# RPi-HAT_BUS-Controller_V0_7.net
KiCad netlist of a schematic drawn in EAGLE
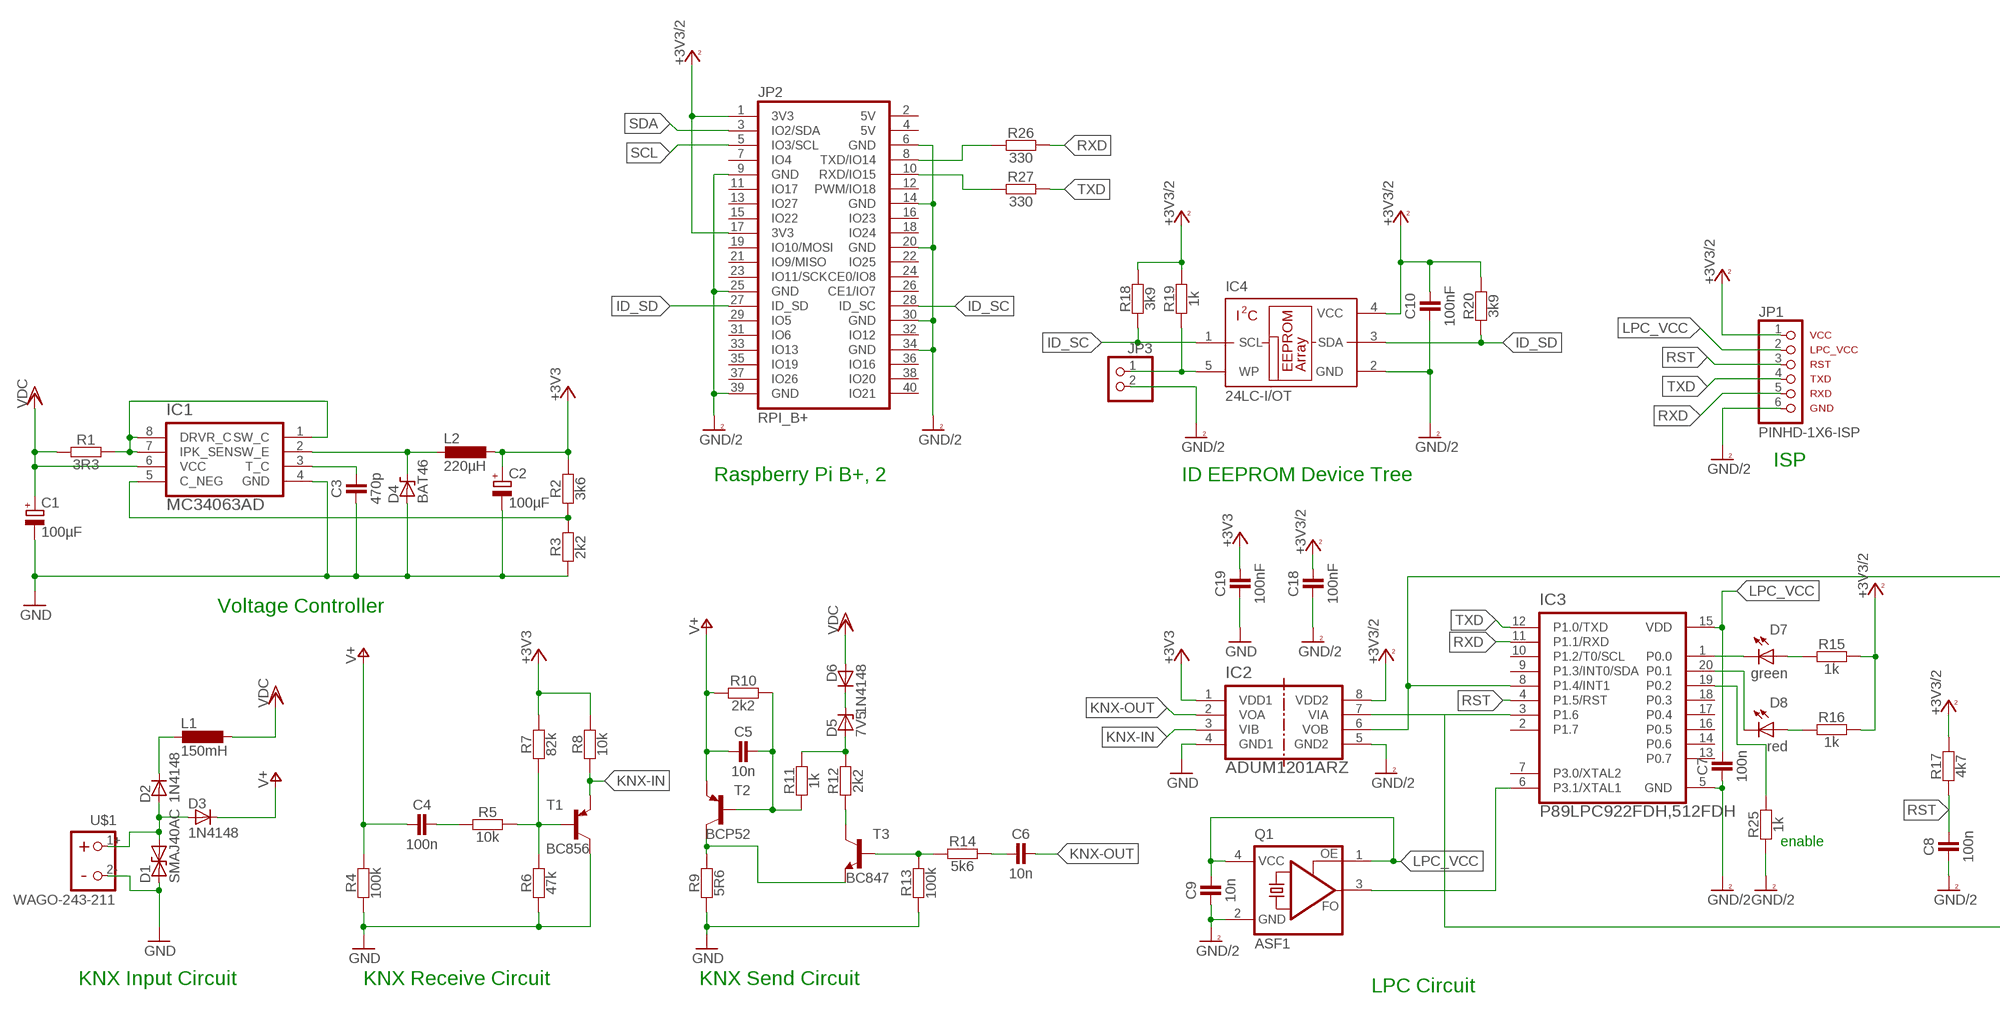
[diagram p0: schematic, sheet 1, part 1 of 2]
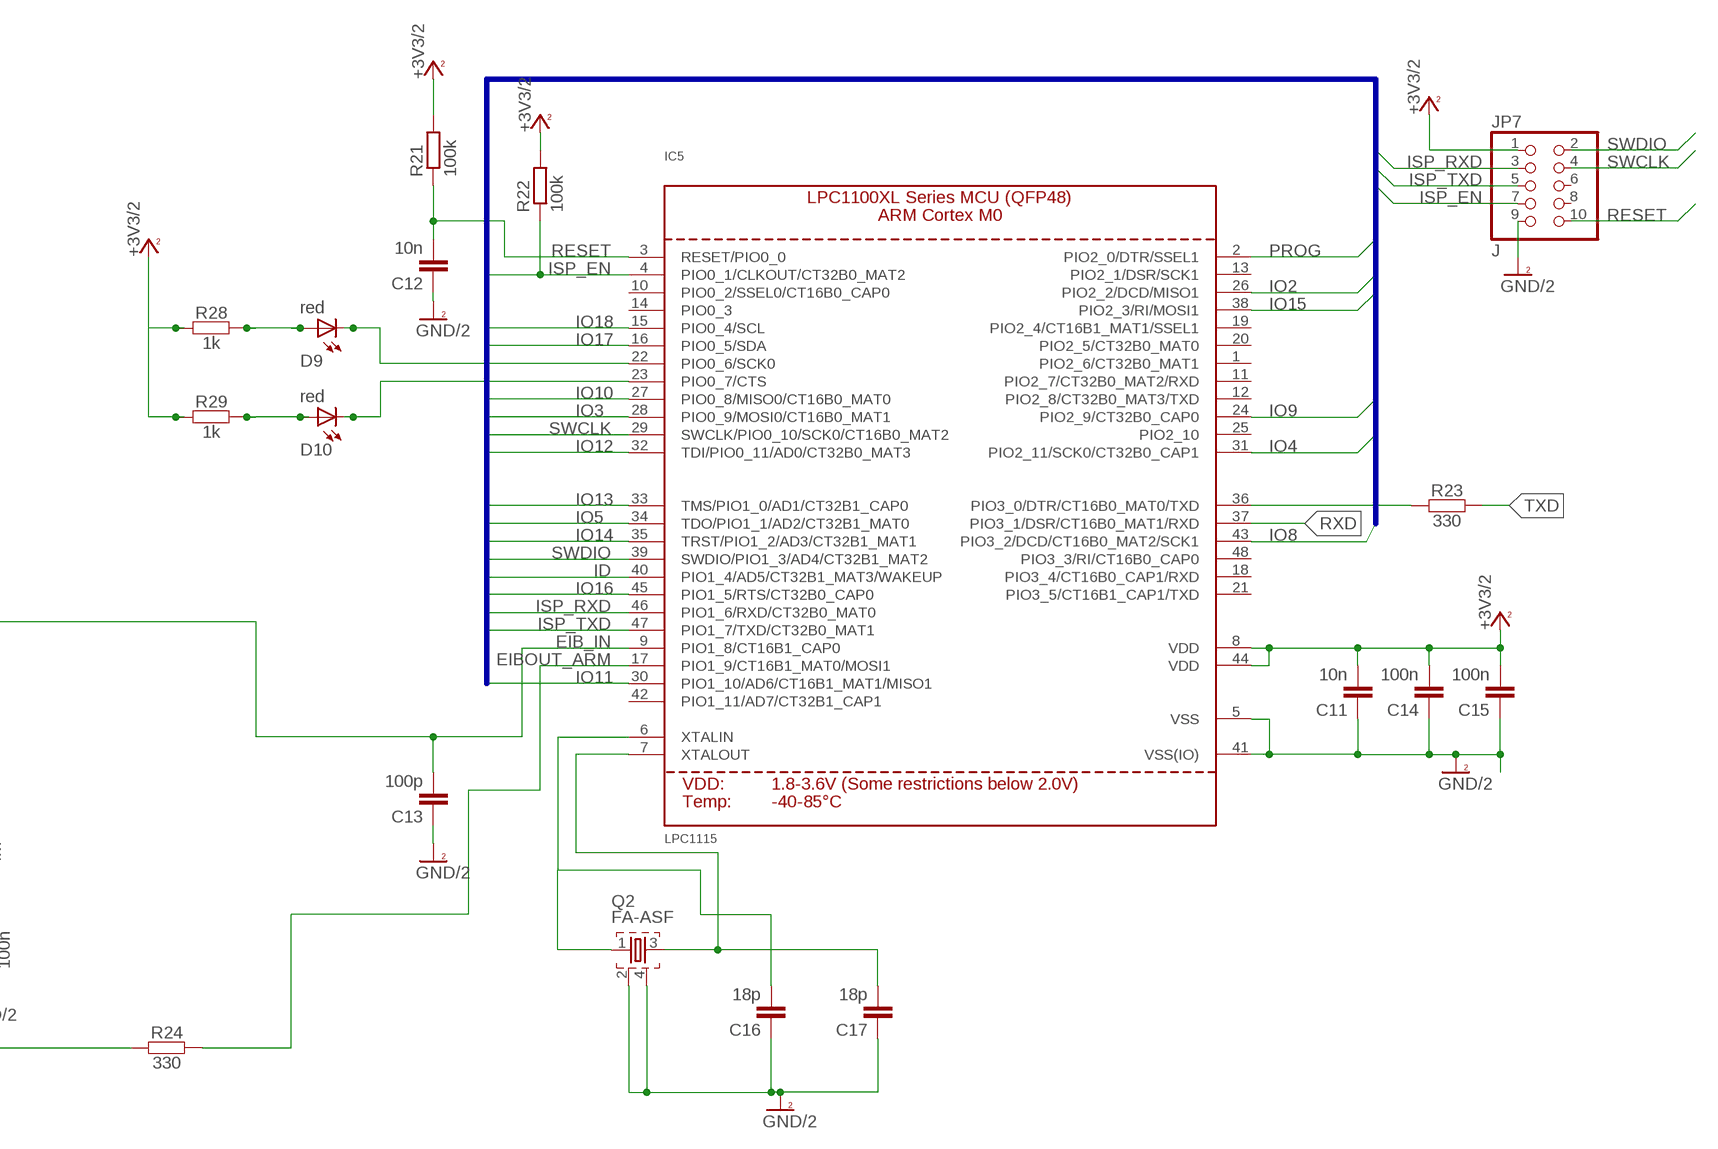
[diagram p1: schematic, sheet 1, part 2 of 2]

(export (version "E")
  (design (tool "Eeschema 10.0.6"))
  (components
    (comp (ref "C1")
      (value "100µF")
      (footprint "eagle-import:PANASONIC_D")
      (libsource (lib "eagle-import") (part "100µF,35V"))
    )
    (comp (ref "C2")
      (value "100µF")
      (footprint "eagle-import:PANASONIC_C")
      (libsource (lib "eagle-import") (part "100µF,6.3V"))
    )
    (comp (ref "C3")
      (value "470p")
      (footprint "eagle-import:R1206")
      (libsource (lib "eagle-import") (part "CAPACITORC1206"))
    )
    (comp (ref "C4")
      (value "100n")
      (footprint "eagle-import:R1206")
      (libsource (lib "eagle-import") (part "CAPACITORC1206"))
    )
    (comp (ref "C5")
      (value "10n")
      (footprint "eagle-import:R1206")
      (libsource (lib "eagle-import") (part "CAPACITORC1206"))
    )
    (comp (ref "C6")
      (value "10n")
      (footprint "eagle-import:R1206")
      (libsource (lib "eagle-import") (part "CAPACITORC1206"))
    )
    (comp (ref "C7")
      (value "100n")
      (footprint "eagle-import:R1206")
      (libsource (lib "eagle-import") (part "CAPACITORC1206"))
    )
    (comp (ref "C8")
      (value "100n")
      (footprint "eagle-import:R1206")
      (libsource (lib "eagle-import") (part "CAPACITORC1206"))
    )
    (comp (ref "C9")
      (value "10n")
      (footprint "eagle-import:R1206")
      (libsource (lib "eagle-import") (part "CAPACITORC1206"))
    )
    (comp (ref "C10")
      (value "100nF")
      (footprint "eagle-import:R1206")
      (libsource (lib "eagle-import") (part "CAPACITORC1206"))
    )
    (comp (ref "C11")
      (value "10n")
      (footprint "eagle-import:C1206")
      (libsource (lib "eagle-import") (part "C-EUC1206"))
    )
    (comp (ref "C12")
      (value "10n")
      (footprint "eagle-import:C1206")
      (libsource (lib "eagle-import") (part "C-EUC1206"))
    )
    (comp (ref "C13")
      (value "100p")
      (footprint "eagle-import:C1206")
      (libsource (lib "eagle-import") (part "C-EUC1206"))
    )
    (comp (ref "C14")
      (value "100n")
      (footprint "eagle-import:C1206")
      (libsource (lib "eagle-import") (part "C-EUC1206"))
    )
    (comp (ref "C15")
      (value "100n")
      (footprint "eagle-import:C1206")
      (libsource (lib "eagle-import") (part "C-EUC1206"))
    )
    (comp (ref "C16")
      (value "18p")
      (footprint "eagle-import:C1206")
      (libsource (lib "eagle-import") (part "C-EUC1206"))
    )
    (comp (ref "C17")
      (value "18p")
      (footprint "eagle-import:C1206")
      (libsource (lib "eagle-import") (part "C-EUC1206"))
    )
    (comp (ref "C18")
      (value "100nF")
      (footprint "eagle-import:R1206")
      (libsource (lib "eagle-import") (part "CAPACITORC1206"))
    )
    (comp (ref "C19")
      (value "100nF")
      (footprint "eagle-import:R1206")
      (libsource (lib "eagle-import") (part "CAPACITORC1206"))
    )
    (comp (ref "D1")
      (value "SMAJ40AC")
      (footprint "eagle-import:DO-214AC")
      (libsource (lib "eagle-import") (part "SMAJ40AC"))
    )
    (comp (ref "D2")
      (value "1N4148")
      (footprint "eagle-import:MINIMELF")
      (libsource (lib "eagle-import") (part "1N4148MINIMELF"))
    )
    (comp (ref "D3")
      (value "1N4148")
      (footprint "eagle-import:MINIMELF")
      (libsource (lib "eagle-import") (part "1N4148MINIMELF"))
    )
    (comp (ref "D4")
      (value "BAT46")
      (footprint "eagle-import:MINIMELF")
      (libsource (lib "eagle-import") (part "BAT46"))
    )
    (comp (ref "D5")
      (value "7V5")
      (footprint "eagle-import:MINIMELF")
      (libsource (lib "eagle-import") (part "Z-DIODE"))
    )
    (comp (ref "D6")
      (value "1N4148")
      (footprint "eagle-import:MINIMELF")
      (libsource (lib "eagle-import") (part "Diode_for_Selfbus-Projects_1N4148MINIMELF"))
    )
    (comp (ref "D7")
      (value "green")
      (footprint "eagle-import:CHIPLED_1206")
      (libsource (lib "eagle-import") (part "LED1206"))
    )
    (comp (ref "D8")
      (value "red")
      (footprint "eagle-import:CHIPLED_1206")
      (libsource (lib "eagle-import") (part "LED1206"))
    )
    (comp (ref "D9")
      (value "red")
      (footprint "eagle-import:CHIPLED_1206")
      (libsource (lib "eagle-import") (part "LED1206"))
    )
    (comp (ref "D10")
      (value "red")
      (footprint "eagle-import:CHIPLED_1206")
      (libsource (lib "eagle-import") (part "LED1206"))
    )
    (comp (ref "IC1")
      (value "MC34063AD")
      (footprint "eagle-import:SOIC127P600X175-8N")
      (libsource (lib "eagle-import") (part "MC34063AD"))
    )
    (comp (ref "IC2")
      (value "ADUM1201ARZ")
      (footprint "eagle-import:SOIC127P600X175-8N")
      (libsource (lib "eagle-import") (part "ADUM1201ARZ"))
    )
    (comp (ref "IC3")
      (value "P89LPC922FDH,512FDH")
      (footprint "eagle-import:SOP65P640X110-20N")
      (fields (field (name "MPN") "P89LPC922FDH,512"))
      (libsource (lib "eagle-import") (part "P89LPC922FDH,512FDH"))
    )
    (comp (ref "IC4")
      (value "24LC-I/OT")
      (footprint "eagle-import:SOT23-5")
      (libsource (lib "eagle-import") (part "24LC-I/OT"))
    )
    (comp (ref "IC5")
      (value "LPC1115")
      (footprint "eagle-import:LQFP48")
      (libsource (lib "eagle-import") (part "LPC1113/4/5_QFP48_XLSERIES"))
    )
    (comp (ref "JP1")
      (value "PINHD-1X6-ISP")
      (footprint "eagle-import:1X06")
      (libsource (lib "eagle-import") (part "PINHD-1X6-ISP"))
    )
    (comp (ref "JP2")
      (value "RPI_B+")
      (footprint "eagle-import:RPI-B+HAT")
      (libsource (lib "eagle-import") (part "RPI_B+"))
    )
    (comp (ref "JP3")
      (value "PINHD-1X2")
      (footprint "eagle-import:1X02")
      (libsource (lib "eagle-import") (part "PINHD-1X2"))
    )
    (comp (ref "JP7")
      (value "J")
      (footprint "eagle-import:2X05M")
      (libsource (lib "eagle-import") (part "PINHD-2X05_2.00"))
    )
    (comp (ref "L1")
      (value "150mH")
      (footprint "eagle-import:11P-L1")
      (libsource (lib "eagle-import") (part "150MH-L11PL1"))
    )
    (comp (ref "L2")
      (value "220µH")
      (footprint "eagle-import:2200-11.43")
      (libsource (lib "eagle-import") (part "220µH-SMCC11.43"))
    )
    (comp (ref "Q1")
      (value "ASF1")
      (footprint "eagle-import:ASF")
      (libsource (lib "eagle-import") (part "ASF1"))
    )
    (comp (ref "Q2")
      (value "FA-ASF")
      (footprint "eagle-import:ASF")
      (libsource (lib "eagle-import") (part "FA-ASF"))
    )
    (comp (ref "R1")
      (value "3R3")
      (footprint "eagle-import:R1206")
      (libsource (lib "eagle-import") (part "RESISTORR1206"))
    )
    (comp (ref "R2")
      (value "3k6")
      (footprint "eagle-import:R1206")
      (libsource (lib "eagle-import") (part "RESISTORR1206"))
    )
    (comp (ref "R3")
      (value "2k2")
      (footprint "eagle-import:R1206")
      (libsource (lib "eagle-import") (part "RESISTORR1206"))
    )
    (comp (ref "R4")
      (value "100k")
      (footprint "eagle-import:R1206")
      (libsource (lib "eagle-import") (part "RESISTORR1206"))
    )
    (comp (ref "R5")
      (value "10k")
      (footprint "eagle-import:R1206")
      (libsource (lib "eagle-import") (part "RESISTORR1206"))
    )
    (comp (ref "R6")
      (value "47k")
      (footprint "eagle-import:R1206")
      (libsource (lib "eagle-import") (part "RESISTORR1206"))
    )
    (comp (ref "R7")
      (value "82k")
      (footprint "eagle-import:R1206")
      (libsource (lib "eagle-import") (part "RESISTORR1206"))
    )
    (comp (ref "R8")
      (value "10k")
      (footprint "eagle-import:R1206")
      (libsource (lib "eagle-import") (part "RESISTORR1206"))
    )
    (comp (ref "R9")
      (value "5R6")
      (footprint "eagle-import:R1206")
      (libsource (lib "eagle-import") (part "RESISTORR1206"))
    )
    (comp (ref "R10")
      (value "2k2")
      (footprint "eagle-import:R1206")
      (libsource (lib "eagle-import") (part "RESISTORR1206"))
    )
    (comp (ref "R11")
      (value "1k")
      (footprint "eagle-import:R1206")
      (libsource (lib "eagle-import") (part "RESISTORR1206"))
    )
    (comp (ref "R12")
      (value "2k2")
      (footprint "eagle-import:R1206")
      (libsource (lib "eagle-import") (part "RESISTORR1206"))
    )
    (comp (ref "R13")
      (value "100k")
      (footprint "eagle-import:R1206")
      (libsource (lib "eagle-import") (part "RESISTORR1206"))
    )
    (comp (ref "R14")
      (value "5k6")
      (footprint "eagle-import:R1206")
      (libsource (lib "eagle-import") (part "RESISTORR1206"))
    )
    (comp (ref "R15")
      (value "1k")
      (footprint "eagle-import:R1206")
      (libsource (lib "eagle-import") (part "RESISTORR1206"))
    )
    (comp (ref "R16")
      (value "1k")
      (footprint "eagle-import:R1206")
      (libsource (lib "eagle-import") (part "RESISTORR1206"))
    )
    (comp (ref "R17")
      (value "4k7")
      (footprint "eagle-import:R1206")
      (libsource (lib "eagle-import") (part "RESISTORR1206"))
    )
    (comp (ref "R18")
      (value "3k9")
      (footprint "eagle-import:R1206")
      (libsource (lib "eagle-import") (part "RESISTORR1206"))
    )
    (comp (ref "R19")
      (value "1k")
      (footprint "eagle-import:R1206")
      (libsource (lib "eagle-import") (part "RESISTORR1206"))
    )
    (comp (ref "R20")
      (value "3k9")
      (footprint "eagle-import:R1206")
      (libsource (lib "eagle-import") (part "RESISTORR1206"))
    )
    (comp (ref "R21")
      (value "100k")
      (footprint "eagle-import:R1206")
      (libsource (lib "eagle-import") (part "R-EU_R1206"))
    )
    (comp (ref "R22")
      (value "100k")
      (footprint "eagle-import:R1206")
      (libsource (lib "eagle-import") (part "R-EU_R1206"))
    )
    (comp (ref "R23")
      (value "330")
      (footprint "eagle-import:R1206")
      (libsource (lib "eagle-import") (part "RESISTORR1206"))
    )
    (comp (ref "R24")
      (value "330")
      (footprint "eagle-import:R1206")
      (libsource (lib "eagle-import") (part "RESISTORR1206"))
    )
    (comp (ref "R25")
      (value "1k")
      (footprint "eagle-import:R1206")
      (libsource (lib "eagle-import") (part "RESISTORR1206"))
    )
    (comp (ref "R26")
      (value "330")
      (footprint "eagle-import:R1206")
      (libsource (lib "eagle-import") (part "RESISTORR1206"))
    )
    (comp (ref "R27")
      (value "330")
      (footprint "eagle-import:R1206")
      (libsource (lib "eagle-import") (part "RESISTORR1206"))
    )
    (comp (ref "R28")
      (value "1k")
      (footprint "eagle-import:R1206")
      (libsource (lib "eagle-import") (part "RESISTORR1206"))
    )
    (comp (ref "R29")
      (value "1k")
      (footprint "eagle-import:R1206")
      (libsource (lib "eagle-import") (part "RESISTORR1206"))
    )
    (comp (ref "T1")
      (value "BC856")
      (footprint "eagle-import:SOT23")
      (libsource (lib "eagle-import") (part "PNPBC856"))
    )
    (comp (ref "T2")
      (value "BCP52")
      (footprint "eagle-import:SOT223")
      (libsource (lib "eagle-import") (part "PNPBCP52"))
    )
    (comp (ref "T3")
      (value "BC847")
      (footprint "eagle-import:SOT23")
      (libsource (lib "eagle-import") (part "NPN-BC847"))
    )
    (comp (ref "U$1")
      (value "WAGO-243-211")
      (footprint "eagle-import:WAGO-243-211")
      (libsource (lib "eagle-import") (part "WAGO-243-211"))
    )
  )
  (nets
    (net (code "1") (name "+3V3") (class "Default")
      (node (ref "C19") (pin "2") (pinfunction "2_2") (pintype "passive"))
      (node (ref "C2") (pin "+") (pinfunction "+_+") (pintype "passive"))
      (node (ref "IC2") (pin "1") (pinfunction "VDD1_1") (pintype "power_in"))
      (node (ref "L2") (pin "1") (pinfunction "1_1") (pintype "passive"))
      (node (ref "R2") (pin "2") (pinfunction "2_2") (pintype "passive"))
      (node (ref "R7") (pin "2") (pinfunction "2_2") (pintype "passive"))
      (node (ref "R8") (pin "2") (pinfunction "2_2") (pintype "passive"))
    )
    (net (code "2") (name "+3V3{slash}2") (class "Default")
      (node (ref "C10") (pin "2") (pinfunction "2_2") (pintype "passive"))
      (node (ref "C11") (pin "2") (pinfunction "2_2") (pintype "passive"))
      (node (ref "C14") (pin "2") (pinfunction "2_2") (pintype "passive"))
      (node (ref "C15") (pin "2") (pinfunction "2_2") (pintype "passive"))
      (node (ref "C18") (pin "2") (pinfunction "2_2") (pintype "passive"))
      (node (ref "IC2") (pin "8") (pinfunction "VDD2_8") (pintype "power_in"))
      (node (ref "IC4") (pin "4") (pinfunction "VCC_4") (pintype "power_in"))
      (node (ref "IC5") (pin "44") (pinfunction "VDD_44") (pintype "power_in"))
      (node (ref "IC5") (pin "8") (pinfunction "VDD_8") (pintype "power_in"))
      (node (ref "JP1") (pin "1") (pinfunction "1_1") (pintype "passive"))
      (node (ref "JP2") (pin "1") (pinfunction "3V3_1") (pintype "passive"))
      (node (ref "JP2") (pin "17") (pinfunction "3V3_17") (pintype "passive"))
      (node (ref "JP7") (pin "1") (pinfunction "1_1") (pintype "passive"))
      (node (ref "R15") (pin "2") (pinfunction "2_2") (pintype "passive"))
      (node (ref "R16") (pin "2") (pinfunction "2_2") (pintype "passive"))
      (node (ref "R17") (pin "2") (pinfunction "2_2") (pintype "passive"))
      (node (ref "R18") (pin "2") (pinfunction "2_2") (pintype "passive"))
      (node (ref "R19") (pin "2") (pinfunction "2_2") (pintype "passive"))
      (node (ref "R20") (pin "2") (pinfunction "2_2") (pintype "passive"))
      (node (ref "R21") (pin "2") (pinfunction "2_2") (pintype "passive"))
      (node (ref "R22") (pin "2") (pinfunction "2_2") (pintype "passive"))
      (node (ref "R28") (pin "1") (pinfunction "1_1") (pintype "passive"))
      (node (ref "R29") (pin "1") (pinfunction "1_1") (pintype "passive"))
    )
    (net (code "3") (name "/EIBOUT_ARM") (class "Default")
      (node (ref "IC5") (pin "17") (pinfunction "PIO1_9/CT16B1_MAT0/MOSI1_17") (pintype "bidirectional"))
      (node (ref "R24") (pin "2") (pinfunction "2_2") (pintype "passive"))
    )
    (net (code "4") (name "/EIB_IN") (class "Default")
      (node (ref "C13") (pin "2") (pinfunction "2_2") (pintype "passive"))
      (node (ref "IC2") (pin "6") (pinfunction "VOB_6") (pintype "output"))
      (node (ref "IC3") (pin "8") (pinfunction "P1.4/INT1_8") (pintype "bidirectional"))
      (node (ref "IC5") (pin "9") (pinfunction "PIO1_8/CT16B1_CAP0_9") (pintype "bidirectional"))
    )
    (net (code "5") (name "/ID") (class "Default")
      (node (ref "IC5") (pin "40") (pinfunction "PIO1_4/AD5/CT32B1_MAT3/WAKEUP_40") (pintype "bidirectional"))
    )
    (net (code "6") (name "/IO2") (class "Default")
      (node (ref "IC5") (pin "26") (pinfunction "PIO2_2/DCD/MISO1_26") (pintype "bidirectional"))
    )
    (net (code "7") (name "/IO3") (class "Default")
      (node (ref "IC5") (pin "28") (pinfunction "PIO0_9/MOSI0/CT16B0_MAT1_28") (pintype "bidirectional"))
    )
    (net (code "8") (name "/IO4") (class "Default")
      (node (ref "IC5") (pin "31") (pinfunction "PIO2_11/SCK0/CT32B0_CAP1_31") (pintype "bidirectional"))
    )
    (net (code "9") (name "/IO5") (class "Default")
      (node (ref "IC5") (pin "34") (pinfunction "TDO/PIO1_1/AD2/CT32B1_MAT0_34") (pintype "bidirectional"))
    )
    (net (code "10") (name "/IO8") (class "Default")
      (node (ref "IC5") (pin "43") (pinfunction "PIO3_2/DCD/CT16B0_MAT2/SCK1_43") (pintype "bidirectional"))
    )
    (net (code "11") (name "/IO9") (class "Default")
      (node (ref "IC5") (pin "24") (pinfunction "PIO2_9/CT32B0_CAP0_24") (pintype "bidirectional"))
    )
    (net (code "12") (name "/IO10") (class "Default")
      (node (ref "IC5") (pin "27") (pinfunction "PIO0_8/MISO0/CT16B0_MAT0_27") (pintype "bidirectional"))
    )
    (net (code "13") (name "/IO11") (class "Default")
      (node (ref "IC5") (pin "30") (pinfunction "PIO1_10/AD6/CT16B1_MAT1/MISO1_30") (pintype "bidirectional"))
    )
    (net (code "14") (name "/IO12") (class "Default")
      (node (ref "IC5") (pin "32") (pinfunction "TDI/PIO0_11/AD0/CT32B0_MAT3_32") (pintype "bidirectional"))
    )
    (net (code "15") (name "/IO13") (class "Default")
      (node (ref "IC5") (pin "33") (pinfunction "TMS/PIO1_0/AD1/CT32B1_CAP0_33") (pintype "bidirectional"))
    )
    (net (code "16") (name "/IO14") (class "Default")
      (node (ref "IC5") (pin "35") (pinfunction "TRST/PIO1_2/AD3/CT32B1_MAT1_35") (pintype "bidirectional"))
    )
    (net (code "17") (name "/IO15") (class "Default")
      (node (ref "IC5") (pin "38") (pinfunction "PIO2_3/RI/MOSI1_38") (pintype "bidirectional"))
    )
    (net (code "18") (name "/IO16") (class "Default")
      (node (ref "IC5") (pin "45") (pinfunction "PIO1_5/RTS/CT32B0_CAP0_45") (pintype "bidirectional"))
    )
    (net (code "19") (name "/IO17") (class "Default")
      (node (ref "IC5") (pin "16") (pinfunction "PIO0_5/SDA_16") (pintype "bidirectional"))
    )
    (net (code "20") (name "/IO18") (class "Default")
      (node (ref "IC5") (pin "15") (pinfunction "PIO0_4/SCL_15") (pintype "bidirectional"))
    )
    (net (code "21") (name "/ISP_EN") (class "Default")
      (node (ref "IC5") (pin "4") (pinfunction "PIO0_1/CLKOUT/CT32B0_MAT2_4") (pintype "bidirectional"))
      (node (ref "JP7") (pin "7") (pinfunction "7_7") (pintype "passive"))
      (node (ref "R22") (pin "1") (pinfunction "1_1") (pintype "passive"))
    )
    (net (code "22") (name "/ISP_RXD") (class "Default")
      (node (ref "IC5") (pin "46") (pinfunction "PIO1_6/RXD/CT32B0_MAT0_46") (pintype "bidirectional"))
      (node (ref "JP7") (pin "3") (pinfunction "3_3") (pintype "passive"))
    )
    (net (code "23") (name "/ISP_TXD") (class "Default")
      (node (ref "IC5") (pin "47") (pinfunction "PIO1_7/TXD/CT32B0_MAT1_47") (pintype "bidirectional"))
      (node (ref "JP7") (pin "5") (pinfunction "5_5") (pintype "passive"))
    )
    (net (code "24") (name "/PROG") (class "Default")
      (node (ref "IC5") (pin "2") (pinfunction "PIO2_0/DTR/SSEL1_2") (pintype "bidirectional"))
    )
    (net (code "25") (name "/RESET") (class "Default")
      (node (ref "C12") (pin "2") (pinfunction "2_2") (pintype "passive"))
      (node (ref "IC5") (pin "3") (pinfunction "RESET/PIO0_0_3") (pintype "bidirectional"))
      (node (ref "JP7") (pin "10") (pinfunction "10_10") (pintype "passive"))
      (node (ref "R21") (pin "1") (pinfunction "1_1") (pintype "passive"))
    )
    (net (code "26") (name "/SWCLK") (class "Default")
      (node (ref "IC5") (pin "29") (pinfunction "SWCLK/PIO0_10/SCK0/CT16B0_MAT2_29") (pintype "bidirectional"))
      (node (ref "JP7") (pin "4") (pinfunction "4_4") (pintype "passive"))
    )
    (net (code "27") (name "/SWDIO") (class "Default")
      (node (ref "IC5") (pin "39") (pinfunction "SWDIO/PIO1_3/AD4/CT32B1_MAT2_39") (pintype "bidirectional"))
      (node (ref "JP7") (pin "2") (pinfunction "2_2") (pintype "passive"))
    )
    (net (code "28") (name "GND") (class "Default")
      (node (ref "C1") (pin "-") (pinfunction "-_-") (pintype "passive"))
      (node (ref "C19") (pin "1") (pinfunction "1_1") (pintype "passive"))
      (node (ref "C2") (pin "-") (pinfunction "-_-") (pintype "passive"))
      (node (ref "C3") (pin "1") (pinfunction "1_1") (pintype "passive"))
      (node (ref "D1") (pin "A") (pinfunction "A_A") (pintype "passive"))
      (node (ref "D4") (pin "A") (pinfunction "A_A") (pintype "passive"))
      (node (ref "IC1") (pin "4") (pinfunction "GND_4") (pintype "passive"))
      (node (ref "IC2") (pin "4") (pinfunction "GND1_4") (pintype "passive"))
      (node (ref "R13") (pin "1") (pinfunction "1_1") (pintype "passive"))
      (node (ref "R3") (pin "1") (pinfunction "1_1") (pintype "passive"))
      (node (ref "R4") (pin "1") (pinfunction "1_1") (pintype "passive"))
      (node (ref "R6") (pin "1") (pinfunction "1_1") (pintype "passive"))
      (node (ref "R9") (pin "1") (pinfunction "1_1") (pintype "passive"))
      (node (ref "T1") (pin "3") (pinfunction "C_3") (pintype "passive"))
      (node (ref "U$1") (pin "2-") (pinfunction "2-_2-") (pintype "passive"))
    )
    (net (code "29") (name "GND{slash}2") (class "Default")
      (node (ref "C10") (pin "1") (pinfunction "1_1") (pintype "passive"))
      (node (ref "C11") (pin "1") (pinfunction "1_1") (pintype "passive"))
      (node (ref "C12") (pin "1") (pinfunction "1_1") (pintype "passive"))
      (node (ref "C13") (pin "1") (pinfunction "1_1") (pintype "passive"))
      (node (ref "C14") (pin "1") (pinfunction "1_1") (pintype "passive"))
      (node (ref "C15") (pin "1") (pinfunction "1_1") (pintype "passive"))
      (node (ref "C16") (pin "1") (pinfunction "1_1") (pintype "passive"))
      (node (ref "C17") (pin "1") (pinfunction "1_1") (pintype "passive"))
      (node (ref "C18") (pin "1") (pinfunction "1_1") (pintype "passive"))
      (node (ref "C7") (pin "1") (pinfunction "1_1") (pintype "passive"))
      (node (ref "C8") (pin "1") (pinfunction "1_1") (pintype "passive"))
      (node (ref "C9") (pin "1") (pinfunction "1_1") (pintype "passive"))
      (node (ref "IC2") (pin "5") (pinfunction "GND2_5") (pintype "passive"))
      (node (ref "IC3") (pin "5") (pinfunction "GND_5") (pintype "passive"))
      (node (ref "IC4") (pin "2") (pinfunction "GND_2") (pintype "power_in"))
      (node (ref "IC5") (pin "41") (pinfunction "VSS(IO)_41") (pintype "power_in"))
      (node (ref "IC5") (pin "5") (pinfunction "VSS_5") (pintype "power_in"))
      (node (ref "JP1") (pin "6") (pinfunction "6_6") (pintype "passive"))
      (node (ref "JP2") (pin "14") (pinfunction "GND_14") (pintype "passive"))
      (node (ref "JP2") (pin "20") (pinfunction "GND_20") (pintype "passive"))
      (node (ref "JP2") (pin "25") (pinfunction "GND_25") (pintype "passive"))
      (node (ref "JP2") (pin "30") (pinfunction "GND_30") (pintype "bidirectional"))
      (node (ref "JP2") (pin "34") (pinfunction "GND_34") (pintype "bidirectional"))
      (node (ref "JP2") (pin "39") (pinfunction "GND_39") (pintype "bidirectional"))
      (node (ref "JP2") (pin "6") (pinfunction "GND_6") (pintype "passive"))
      (node (ref "JP2") (pin "9") (pinfunction "GND_9") (pintype "passive"))
      (node (ref "JP3") (pin "2") (pinfunction "2_2") (pintype "passive"))
      (node (ref "JP7") (pin "9") (pinfunction "9_9") (pintype "passive"))
      (node (ref "Q1") (pin "2") (pinfunction "GND_2") (pintype "power_in"))
      (node (ref "Q2") (pin "2") (pinfunction "2_2") (pintype "passive"))
      (node (ref "Q2") (pin "4") (pinfunction "4_4") (pintype "passive"))
      (node (ref "R25") (pin "1") (pinfunction "1_1") (pintype "passive"))
    )
    (net (code "30") (name "ID_SC") (class "Default")
      (node (ref "IC4") (pin "1") (pinfunction "SCL_1") (pintype "bidirectional"))
      (node (ref "JP2") (pin "28") (pinfunction "ID_SC_28") (pintype "bidirectional"))
      (node (ref "R18") (pin "1") (pinfunction "1_1") (pintype "passive"))
    )
    (net (code "31") (name "ID_SD") (class "Default")
      (node (ref "IC4") (pin "3") (pinfunction "SDA_3") (pintype "bidirectional"))
      (node (ref "JP2") (pin "27") (pinfunction "ID_SD_27") (pintype "bidirectional"))
      (node (ref "R20") (pin "1") (pinfunction "1_1") (pintype "passive"))
    )
    (net (code "32") (name "KNX-IN") (class "Default")
      (node (ref "IC2") (pin "3") (pinfunction "VIB_3") (pintype "input"))
      (node (ref "R8") (pin "1") (pinfunction "1_1") (pintype "passive"))
      (node (ref "T1") (pin "2") (pinfunction "E_2") (pintype "passive"))
    )
    (net (code "33") (name "KNX-OUT") (class "Default")
      (node (ref "C6") (pin "2") (pinfunction "2_2") (pintype "passive"))
      (node (ref "IC2") (pin "2") (pinfunction "VOA_2") (pintype "output"))
    )
    (net (code "34") (name "LPC_VCC") (class "Default")
      (node (ref "C7") (pin "2") (pinfunction "2_2") (pintype "passive"))
      (node (ref "C9") (pin "2") (pinfunction "2_2") (pintype "passive"))
      (node (ref "IC3") (pin "15") (pinfunction "VDD_15") (pintype "power_in"))
      (node (ref "JP1") (pin "2") (pinfunction "2_2") (pintype "passive"))
      (node (ref "Q1") (pin "1") (pinfunction "OE_1") (pintype "input"))
      (node (ref "Q1") (pin "4") (pinfunction "VCC_4") (pintype "power_in"))
    )
    (net (code "35") (name "Net-(C4-Pad2)") (class "Default")
      (node (ref "C4") (pin "2") (pinfunction "2_2") (pintype "passive"))
      (node (ref "R5") (pin "1") (pinfunction "1_1") (pintype "passive"))
    )
    (net (code "36") (name "Net-(C6-Pad1)") (class "Default")
      (node (ref "C6") (pin "1") (pinfunction "1_1") (pintype "passive"))
      (node (ref "R14") (pin "2") (pinfunction "2_2") (pintype "passive"))
    )
    (net (code "37") (name "Net-(D1-PadC)") (class "Default")
      (node (ref "D1") (pin "C") (pinfunction "C_C") (pintype "passive"))
      (node (ref "D2") (pin "A") (pinfunction "A_A") (pintype "passive"))
      (node (ref "D3") (pin "A") (pinfunction "A_A") (pintype "passive"))
      (node (ref "U$1") (pin "1+") (pinfunction "1+_1+") (pintype "passive"))
    )
    (net (code "38") (name "Net-(D2-PadC)") (class "Default")
      (node (ref "D2") (pin "C") (pinfunction "C_C") (pintype "passive"))
      (node (ref "L1") (pin "2") (pinfunction "2_2") (pintype "passive"))
    )
    (net (code "39") (name "Net-(D5-PadA)") (class "Default")
      (node (ref "D5") (pin "A") (pinfunction "A_A") (pintype "passive"))
      (node (ref "R11") (pin "2") (pinfunction "2_2") (pintype "passive"))
      (node (ref "R12") (pin "2") (pinfunction "2_2") (pintype "passive"))
    )
    (net (code "40") (name "Net-(D5-PadC)") (class "Default")
      (node (ref "D5") (pin "C") (pinfunction "C_C") (pintype "passive"))
      (node (ref "D6") (pin "C") (pinfunction "C_C") (pintype "passive"))
    )
    (net (code "41") (name "Net-(D7-PadA)") (class "Default")
      (node (ref "D7") (pin "A") (pinfunction "A_A") (pintype "passive"))
      (node (ref "R15") (pin "1") (pinfunction "1_1") (pintype "passive"))
    )
    (net (code "42") (name "Net-(D8-PadA)") (class "Default")
      (node (ref "D8") (pin "A") (pinfunction "A_A") (pintype "passive"))
      (node (ref "R16") (pin "1") (pinfunction "1_1") (pintype "passive"))
    )
    (net (code "43") (name "Net-(D9-PadA)") (class "Default")
      (node (ref "D9") (pin "A") (pinfunction "A_A") (pintype "passive"))
      (node (ref "R28") (pin "2") (pinfunction "2_2") (pintype "passive"))
    )
    (net (code "44") (name "Net-(D10-PadA)") (class "Default")
      (node (ref "D10") (pin "A") (pinfunction "A_A") (pintype "passive"))
      (node (ref "R29") (pin "2") (pinfunction "2_2") (pintype "passive"))
    )
    (net (code "45") (name "Net-(IC1-C_NEG)") (class "Default")
      (node (ref "IC1") (pin "5") (pinfunction "C_NEG_5") (pintype "input"))
      (node (ref "R2") (pin "1") (pinfunction "1_1") (pintype "passive"))
      (node (ref "R3") (pin "2") (pinfunction "2_2") (pintype "passive"))
    )
    (net (code "46") (name "Net-(IC1-DRVR_C)") (class "Default")
      (node (ref "IC1") (pin "1") (pinfunction "SW_C_1") (pintype "output"))
      (node (ref "IC1") (pin "7") (pinfunction "IPK_SEN_7") (pintype "input"))
      (node (ref "IC1") (pin "8") (pinfunction "DRVR_C_8") (pintype "input"))
      (node (ref "R1") (pin "2") (pinfunction "2_2") (pintype "passive"))
    )
    (net (code "47") (name "Net-(IC1-SW_E)") (class "Default")
      (node (ref "D4") (pin "C") (pinfunction "C_C") (pintype "passive"))
      (node (ref "IC1") (pin "2") (pinfunction "SW_E_2") (pintype "output"))
      (node (ref "L2") (pin "2") (pinfunction "2_2") (pintype "passive"))
    )
    (net (code "48") (name "Net-(IC1-T_C)") (class "Default")
      (node (ref "C3") (pin "2") (pinfunction "2_2") (pintype "passive"))
      (node (ref "IC1") (pin "3") (pinfunction "T_C_3") (pintype "output"))
    )
    (net (code "49") (name "Net-(IC2-VIA)") (class "Default")
      (node (ref "IC2") (pin "7") (pinfunction "VIA_7") (pintype "input"))
      (node (ref "IC3") (pin "3") (pinfunction "P1.6_3") (pintype "bidirectional"))
      (node (ref "R24") (pin "1") (pinfunction "1_1") (pintype "passive"))
    )
    (net (code "50") (name "Net-(IC3-P0.0)") (class "Default")
      (node (ref "D7") (pin "C") (pinfunction "C_C") (pintype "passive"))
      (node (ref "IC3") (pin "1") (pinfunction "P0.0_1") (pintype "bidirectional"))
    )
    (net (code "51") (name "Net-(IC3-P0.1)") (class "Default")
      (node (ref "D8") (pin "C") (pinfunction "C_C") (pintype "passive"))
      (node (ref "IC3") (pin "20") (pinfunction "P0.1_20") (pintype "bidirectional"))
    )
    (net (code "52") (name "Net-(IC3-P0.2)") (class "Default")
      (node (ref "IC3") (pin "19") (pinfunction "P0.2_19") (pintype "bidirectional"))
      (node (ref "R25") (pin "2") (pinfunction "2_2") (pintype "passive"))
    )
    (net (code "53") (name "Net-(IC3-P3.1{slash}XTAL1)") (class "Default")
      (node (ref "IC3") (pin "6") (pinfunction "P3.1/XTAL1_6") (pintype "bidirectional"))
      (node (ref "Q1") (pin "3") (pinfunction "FO_3") (pintype "output"))
    )
    (net (code "54") (name "Net-(IC4-WP)") (class "Default")
      (node (ref "IC4") (pin "5") (pinfunction "WP_5") (pintype "bidirectional"))
      (node (ref "JP3") (pin "1") (pinfunction "1_1") (pintype "passive"))
      (node (ref "R19") (pin "1") (pinfunction "1_1") (pintype "passive"))
    )
    (net (code "55") (name "Net-(IC5-PIO0_6{slash}SCK0)") (class "Default")
      (node (ref "D9") (pin "C") (pinfunction "C_C") (pintype "passive"))
      (node (ref "IC5") (pin "22") (pinfunction "PIO0_6/SCK0_22") (pintype "bidirectional"))
    )
    (net (code "56") (name "Net-(IC5-PIO0_7{slash}CTS)") (class "Default")
      (node (ref "D10") (pin "C") (pinfunction "C_C") (pintype "passive"))
      (node (ref "IC5") (pin "23") (pinfunction "PIO0_7/CTS_23") (pintype "bidirectional"))
    )
    (net (code "57") (name "Net-(IC5-PIO3_0{slash}DTR{slash}CT16B0_MAT0{slash}TXD)") (class "Default")
      (node (ref "IC5") (pin "36") (pinfunction "PIO3_0/DTR/CT16B0_MAT0/TXD_36") (pintype "bidirectional"))
      (node (ref "R23") (pin "1") (pinfunction "1_1") (pintype "passive"))
    )
    (net (code "58") (name "Net-(IC5-XTALIN)") (class "Default")
      (node (ref "C16") (pin "2") (pinfunction "2_2") (pintype "passive"))
      (node (ref "IC5") (pin "6") (pinfunction "XTALIN_6") (pintype "input"))
      (node (ref "Q2") (pin "1") (pinfunction "1_1") (pintype "passive"))
    )
    (net (code "59") (name "Net-(IC5-XTALOUT)") (class "Default")
      (node (ref "C17") (pin "2") (pinfunction "2_2") (pintype "passive"))
      (node (ref "IC5") (pin "7") (pinfunction "XTALOUT_7") (pintype "output"))
      (node (ref "Q2") (pin "3") (pinfunction "3_3") (pintype "passive"))
    )
    (net (code "60") (name "Net-(JP2-RXD{slash}IO15)") (class "Default")
      (node (ref "JP2") (pin "10") (pinfunction "RXD/IO15_10") (pintype "passive"))
      (node (ref "R27") (pin "1") (pinfunction "1_1") (pintype "passive"))
    )
    (net (code "61") (name "Net-(JP2-TXD{slash}IO14)") (class "Default")
      (node (ref "JP2") (pin "8") (pinfunction "TXD/IO14_8") (pintype "passive"))
      (node (ref "R26") (pin "1") (pinfunction "1_1") (pintype "passive"))
    )
    (net (code "62") (name "Net-(T1-B)") (class "Default")
      (node (ref "R5") (pin "2") (pinfunction "2_2") (pintype "passive"))
      (node (ref "R6") (pin "2") (pinfunction "2_2") (pintype "passive"))
      (node (ref "R7") (pin "1") (pinfunction "1_1") (pintype "passive"))
      (node (ref "T1") (pin "1") (pinfunction "B_1") (pintype "passive"))
    )
    (net (code "63") (name "Net-(T2-B)") (class "Default")
      (node (ref "C5") (pin "2") (pinfunction "2_2") (pintype "passive"))
      (node (ref "R10") (pin "2") (pinfunction "2_2") (pintype "passive"))
      (node (ref "R11") (pin "1") (pinfunction "1_1") (pintype "passive"))
      (node (ref "T2") (pin "1") (pinfunction "B_1") (pintype "passive"))
    )
    (net (code "64") (name "Net-(T3-B)") (class "Default")
      (node (ref "R13") (pin "2") (pinfunction "2_2") (pintype "passive"))
      (node (ref "R14") (pin "1") (pinfunction "1_1") (pintype "passive"))
      (node (ref "T3") (pin "1") (pinfunction "B_1") (pintype "passive"))
    )
    (net (code "65") (name "Net-(T3-C)") (class "Default")
      (node (ref "R12") (pin "1") (pinfunction "1_1") (pintype "passive"))
      (node (ref "T3") (pin "3") (pinfunction "C_3") (pintype "passive"))
    )
    (net (code "66") (name "Net-(T3-E)") (class "Default")
      (node (ref "R9") (pin "2") (pinfunction "2_2") (pintype "passive"))
      (node (ref "T2") (pin "2") (pinfunction "C_2") (pintype "passive"))
      (node (ref "T2") (pin "4") (pinfunction "C_4") (pintype "passive"))
      (node (ref "T3") (pin "2") (pinfunction "E_2") (pintype "passive"))
    )
    (net (code "67") (name "RST") (class "Default")
      (node (ref "C8") (pin "2") (pinfunction "2_2") (pintype "passive"))
      (node (ref "IC3") (pin "4") (pinfunction "P1.5/RST_4") (pintype "input"))
      (node (ref "JP1") (pin "3") (pinfunction "3_3") (pintype "passive"))
      (node (ref "R17") (pin "1") (pinfunction "1_1") (pintype "passive"))
    )
    (net (code "68") (name "RXD") (class "Default")
      (node (ref "IC3") (pin "11") (pinfunction "P1.1/RXD_11") (pintype "bidirectional"))
      (node (ref "IC5") (pin "37") (pinfunction "PIO3_1/DSR/CT16B0_MAT1/RXD_37") (pintype "bidirectional"))
      (node (ref "JP1") (pin "5") (pinfunction "5_5") (pintype "passive"))
      (node (ref "R26") (pin "2") (pinfunction "2_2") (pintype "passive"))
    )
    (net (code "69") (name "SCL") (class "Default")
      (node (ref "JP2") (pin "5") (pinfunction "IO3/SCL_5") (pintype "passive"))
    )
    (net (code "70") (name "SDA") (class "Default")
      (node (ref "JP2") (pin "3") (pinfunction "IO2/SDA_3") (pintype "passive"))
    )
    (net (code "71") (name "TXD") (class "Default")
      (node (ref "IC3") (pin "12") (pinfunction "P1.0/TXD_12") (pintype "bidirectional"))
      (node (ref "JP1") (pin "4") (pinfunction "4_4") (pintype "passive"))
      (node (ref "R23") (pin "2") (pinfunction "2_2") (pintype "passive"))
      (node (ref "R27") (pin "2") (pinfunction "2_2") (pintype "passive"))
    )
    (net (code "72") (name "V+") (class "Default")
      (node (ref "C4") (pin "1") (pinfunction "1_1") (pintype "passive"))
      (node (ref "C5") (pin "1") (pinfunction "1_1") (pintype "passive"))
      (node (ref "D3") (pin "C") (pinfunction "C_C") (pintype "passive"))
      (node (ref "R10") (pin "1") (pinfunction "1_1") (pintype "passive"))
      (node (ref "R4") (pin "2") (pinfunction "2_2") (pintype "passive"))
      (node (ref "T2") (pin "3") (pinfunction "E_3") (pintype "passive"))
    )
    (net (code "73") (name "VDC") (class "Default")
      (node (ref "C1") (pin "+") (pinfunction "+_+") (pintype "passive"))
      (node (ref "D6") (pin "A") (pinfunction "A_A") (pintype "passive"))
      (node (ref "IC1") (pin "6") (pinfunction "VCC_6") (pintype "power_in"))
      (node (ref "L1") (pin "1") (pinfunction "1_1") (pintype "passive"))
      (node (ref "R1") (pin "1") (pinfunction "1_1") (pintype "passive"))
    )
    (net (code "74") (name "unconnected-(IC3-P0.3-Pad18)") (class "Default")
      (node (ref "IC3") (pin "18") (pinfunction "P0.3_18") (pintype "bidirectional"))
    )
    (net (code "75") (name "unconnected-(IC3-P0.4-Pad17)") (class "Default")
      (node (ref "IC3") (pin "17") (pinfunction "P0.4_17") (pintype "bidirectional"))
    )
    (net (code "76") (name "unconnected-(IC3-P0.5-Pad16)") (class "Default")
      (node (ref "IC3") (pin "16") (pinfunction "P0.5_16") (pintype "bidirectional"))
    )
    (net (code "77") (name "unconnected-(IC3-P0.6-Pad14)") (class "Default")
      (node (ref "IC3") (pin "14") (pinfunction "P0.6_14") (pintype "bidirectional"))
    )
    (net (code "78") (name "unconnected-(IC3-P0.7-Pad13)") (class "Default")
      (node (ref "IC3") (pin "13") (pinfunction "P0.7_13") (pintype "passive"))
    )
    (net (code "79") (name "unconnected-(IC3-P1.2{slash}T0{slash}SCL-Pad10)") (class "Default")
      (node (ref "IC3") (pin "10") (pinfunction "P1.2/T0/SCL_10") (pintype "bidirectional"))
    )
    (net (code "80") (name "unconnected-(IC3-P1.3{slash}INT0{slash}SDA-Pad9)") (class "Default")
      (node (ref "IC3") (pin "9") (pinfunction "P1.3/INT0/SDA_9") (pintype "bidirectional"))
    )
    (net (code "81") (name "unconnected-(IC3-P1.7-Pad2)") (class "Default")
      (node (ref "IC3") (pin "2") (pinfunction "P1.7_2") (pintype "bidirectional"))
    )
    (net (code "82") (name "unconnected-(IC3-P3.0{slash}XTAL2-Pad7)") (class "Default")
      (node (ref "IC3") (pin "7") (pinfunction "P3.0/XTAL2_7") (pintype "bidirectional"))
    )
    (net (code "83") (name "unconnected-(IC5-PIO0_2{slash}SSEL0{slash}CT16B0_CAP0-Pad10)") (class "Default")
      (node (ref "IC5") (pin "10") (pinfunction "PIO0_2/SSEL0/CT16B0_CAP0_10") (pintype "bidirectional"))
    )
    (net (code "84") (name "unconnected-(IC5-PIO0_3-Pad14)") (class "Default")
      (node (ref "IC5") (pin "14") (pinfunction "PIO0_3_14") (pintype "bidirectional"))
    )
    (net (code "85") (name "unconnected-(IC5-PIO1_11{slash}AD7{slash}CT32B1_CAP1-Pad42)") (class "Default")
      (node (ref "IC5") (pin "42") (pinfunction "PIO1_11/AD7/CT32B1_CAP1_42") (pintype "bidirectional"))
    )
    (net (code "86") (name "unconnected-(IC5-PIO2_1{slash}DSR{slash}SCK1-Pad13)") (class "Default")
      (node (ref "IC5") (pin "13") (pinfunction "PIO2_1/DSR/SCK1_13") (pintype "bidirectional"))
    )
    (net (code "87") (name "unconnected-(IC5-PIO2_4{slash}CT16B1_MAT1{slash}SSEL1-Pad19)") (class "Default")
      (node (ref "IC5") (pin "19") (pinfunction "PIO2_4/CT16B1_MAT1/SSEL1_19") (pintype "bidirectional"))
    )
    (net (code "88") (name "unconnected-(IC5-PIO2_5{slash}CT32B0_MAT0-Pad20)") (class "Default")
      (node (ref "IC5") (pin "20") (pinfunction "PIO2_5/CT32B0_MAT0_20") (pintype "bidirectional"))
    )
    (net (code "89") (name "unconnected-(IC5-PIO2_6{slash}CT32B0_MAT1-Pad1)") (class "Default")
      (node (ref "IC5") (pin "1") (pinfunction "PIO2_6/CT32B0_MAT1_1") (pintype "bidirectional"))
    )
    (net (code "90") (name "unconnected-(IC5-PIO2_7{slash}CT32B0_MAT2{slash}RXD-Pad11)") (class "Default")
      (node (ref "IC5") (pin "11") (pinfunction "PIO2_7/CT32B0_MAT2/RXD_11") (pintype "bidirectional"))
    )
    (net (code "91") (name "unconnected-(IC5-PIO2_8{slash}CT32B0_MAT3{slash}TXD-Pad12)") (class "Default")
      (node (ref "IC5") (pin "12") (pinfunction "PIO2_8/CT32B0_MAT3/TXD_12") (pintype "bidirectional"))
    )
    (net (code "92") (name "unconnected-(IC5-PIO2_10-Pad25)") (class "Default")
      (node (ref "IC5") (pin "25") (pinfunction "PIO2_10_25") (pintype "bidirectional"))
    )
    (net (code "93") (name "unconnected-(IC5-PIO3_3{slash}RI{slash}CT16B0_CAP0-Pad48)") (class "Default")
      (node (ref "IC5") (pin "48") (pinfunction "PIO3_3/RI/CT16B0_CAP0_48") (pintype "bidirectional"))
    )
    (net (code "94") (name "unconnected-(IC5-PIO3_4{slash}CT16B0_CAP1{slash}RXD-Pad18)") (class "Default")
      (node (ref "IC5") (pin "18") (pinfunction "PIO3_4/CT16B0_CAP1/RXD_18") (pintype "bidirectional"))
    )
    (net (code "95") (name "unconnected-(IC5-PIO3_5{slash}CT16B1_CAP1{slash}TXD-Pad21)") (class "Default")
      (node (ref "IC5") (pin "21") (pinfunction "PIO3_5/CT16B1_CAP1/TXD_21") (pintype "bidirectional"))
    )
    (net (code "96") (name "unconnected-(JP2-5V-Pad2)") (class "Default")
      (node (ref "JP2") (pin "2") (pinfunction "5V_2") (pintype "passive"))
    )
    (net (code "97") (name "unconnected-(JP2-5V-Pad4)") (class "Default")
      (node (ref "JP2") (pin "4") (pinfunction "5V_4") (pintype "passive"))
    )
    (net (code "98") (name "unconnected-(JP2-CE0{slash}IO8-Pad24)") (class "Default")
      (node (ref "JP2") (pin "24") (pinfunction "CE0/IO8_24") (pintype "passive"))
    )
    (net (code "99") (name "unconnected-(JP2-CE1{slash}IO7-Pad26)") (class "Default")
      (node (ref "JP2") (pin "26") (pinfunction "CE1/IO7_26") (pintype "passive"))
    )
    (net (code "100") (name "unconnected-(JP2-IO4-Pad7)") (class "Default")
      (node (ref "JP2") (pin "7") (pinfunction "IO4_7") (pintype "passive"))
    )
    (net (code "101") (name "unconnected-(JP2-IO5-Pad29)") (class "Default")
      (node (ref "JP2") (pin "29") (pinfunction "IO5_29") (pintype "bidirectional"))
    )
    (net (code "102") (name "unconnected-(JP2-IO6-Pad31)") (class "Default")
      (node (ref "JP2") (pin "31") (pinfunction "IO6_31") (pintype "bidirectional"))
    )
    (net (code "103") (name "unconnected-(JP2-IO9{slash}MISO-Pad21)") (class "Default")
      (node (ref "JP2") (pin "21") (pinfunction "IO9/MISO_21") (pintype "passive"))
    )
    (net (code "104") (name "unconnected-(JP2-IO10{slash}MOSI-Pad19)") (class "Default")
      (node (ref "JP2") (pin "19") (pinfunction "IO10/MOSI_19") (pintype "passive"))
    )
    (net (code "105") (name "unconnected-(JP2-IO11{slash}SCK-Pad23)") (class "Default")
      (node (ref "JP2") (pin "23") (pinfunction "IO11/SCK_23") (pintype "passive"))
    )
    (net (code "106") (name "unconnected-(JP2-IO12-Pad32)") (class "Default")
      (node (ref "JP2") (pin "32") (pinfunction "IO12_32") (pintype "bidirectional"))
    )
    (net (code "107") (name "unconnected-(JP2-IO13-Pad33)") (class "Default")
      (node (ref "JP2") (pin "33") (pinfunction "IO13_33") (pintype "bidirectional"))
    )
    (net (code "108") (name "unconnected-(JP2-IO16-Pad36)") (class "Default")
      (node (ref "JP2") (pin "36") (pinfunction "IO16_36") (pintype "bidirectional"))
    )
    (net (code "109") (name "unconnected-(JP2-IO17-Pad11)") (class "Default")
      (node (ref "JP2") (pin "11") (pinfunction "IO17_11") (pintype "passive"))
    )
    (net (code "110") (name "unconnected-(JP2-IO19-Pad35)") (class "Default")
      (node (ref "JP2") (pin "35") (pinfunction "IO19_35") (pintype "bidirectional"))
    )
    (net (code "111") (name "unconnected-(JP2-IO20-Pad38)") (class "Default")
      (node (ref "JP2") (pin "38") (pinfunction "IO20_38") (pintype "bidirectional"))
    )
    (net (code "112") (name "unconnected-(JP2-IO21-Pad40)") (class "Default")
      (node (ref "JP2") (pin "40") (pinfunction "IO21_40") (pintype "bidirectional"))
    )
    (net (code "113") (name "unconnected-(JP2-IO22-Pad15)") (class "Default")
      (node (ref "JP2") (pin "15") (pinfunction "IO22_15") (pintype "passive"))
    )
    (net (code "114") (name "unconnected-(JP2-IO23-Pad16)") (class "Default")
      (node (ref "JP2") (pin "16") (pinfunction "IO23_16") (pintype "passive"))
    )
    (net (code "115") (name "unconnected-(JP2-IO24-Pad18)") (class "Default")
      (node (ref "JP2") (pin "18") (pinfunction "IO24_18") (pintype "passive"))
    )
    (net (code "116") (name "unconnected-(JP2-IO25-Pad22)") (class "Default")
      (node (ref "JP2") (pin "22") (pinfunction "IO25_22") (pintype "passive"))
    )
    (net (code "117") (name "unconnected-(JP2-IO26-Pad37)") (class "Default")
      (node (ref "JP2") (pin "37") (pinfunction "IO26_37") (pintype "bidirectional"))
    )
    (net (code "118") (name "unconnected-(JP2-IO27-Pad13)") (class "Default")
      (node (ref "JP2") (pin "13") (pinfunction "IO27_13") (pintype "passive"))
    )
    (net (code "119") (name "unconnected-(JP2-PWM{slash}IO18-Pad12)") (class "Default")
      (node (ref "JP2") (pin "12") (pinfunction "PWM/IO18_12") (pintype "passive"))
    )
    (net (code "120") (name "unconnected-(JP7-Pad6)") (class "Default")
      (node (ref "JP7") (pin "6") (pinfunction "6_6") (pintype "passive"))
    )
    (net (code "121") (name "unconnected-(JP7-Pad8)") (class "Default")
      (node (ref "JP7") (pin "8") (pinfunction "8_8") (pintype "passive"))
    )
  )
)
